# PCB_Telemetria_2020.net
KiCad netlist of a schematic drawn in EAGLE
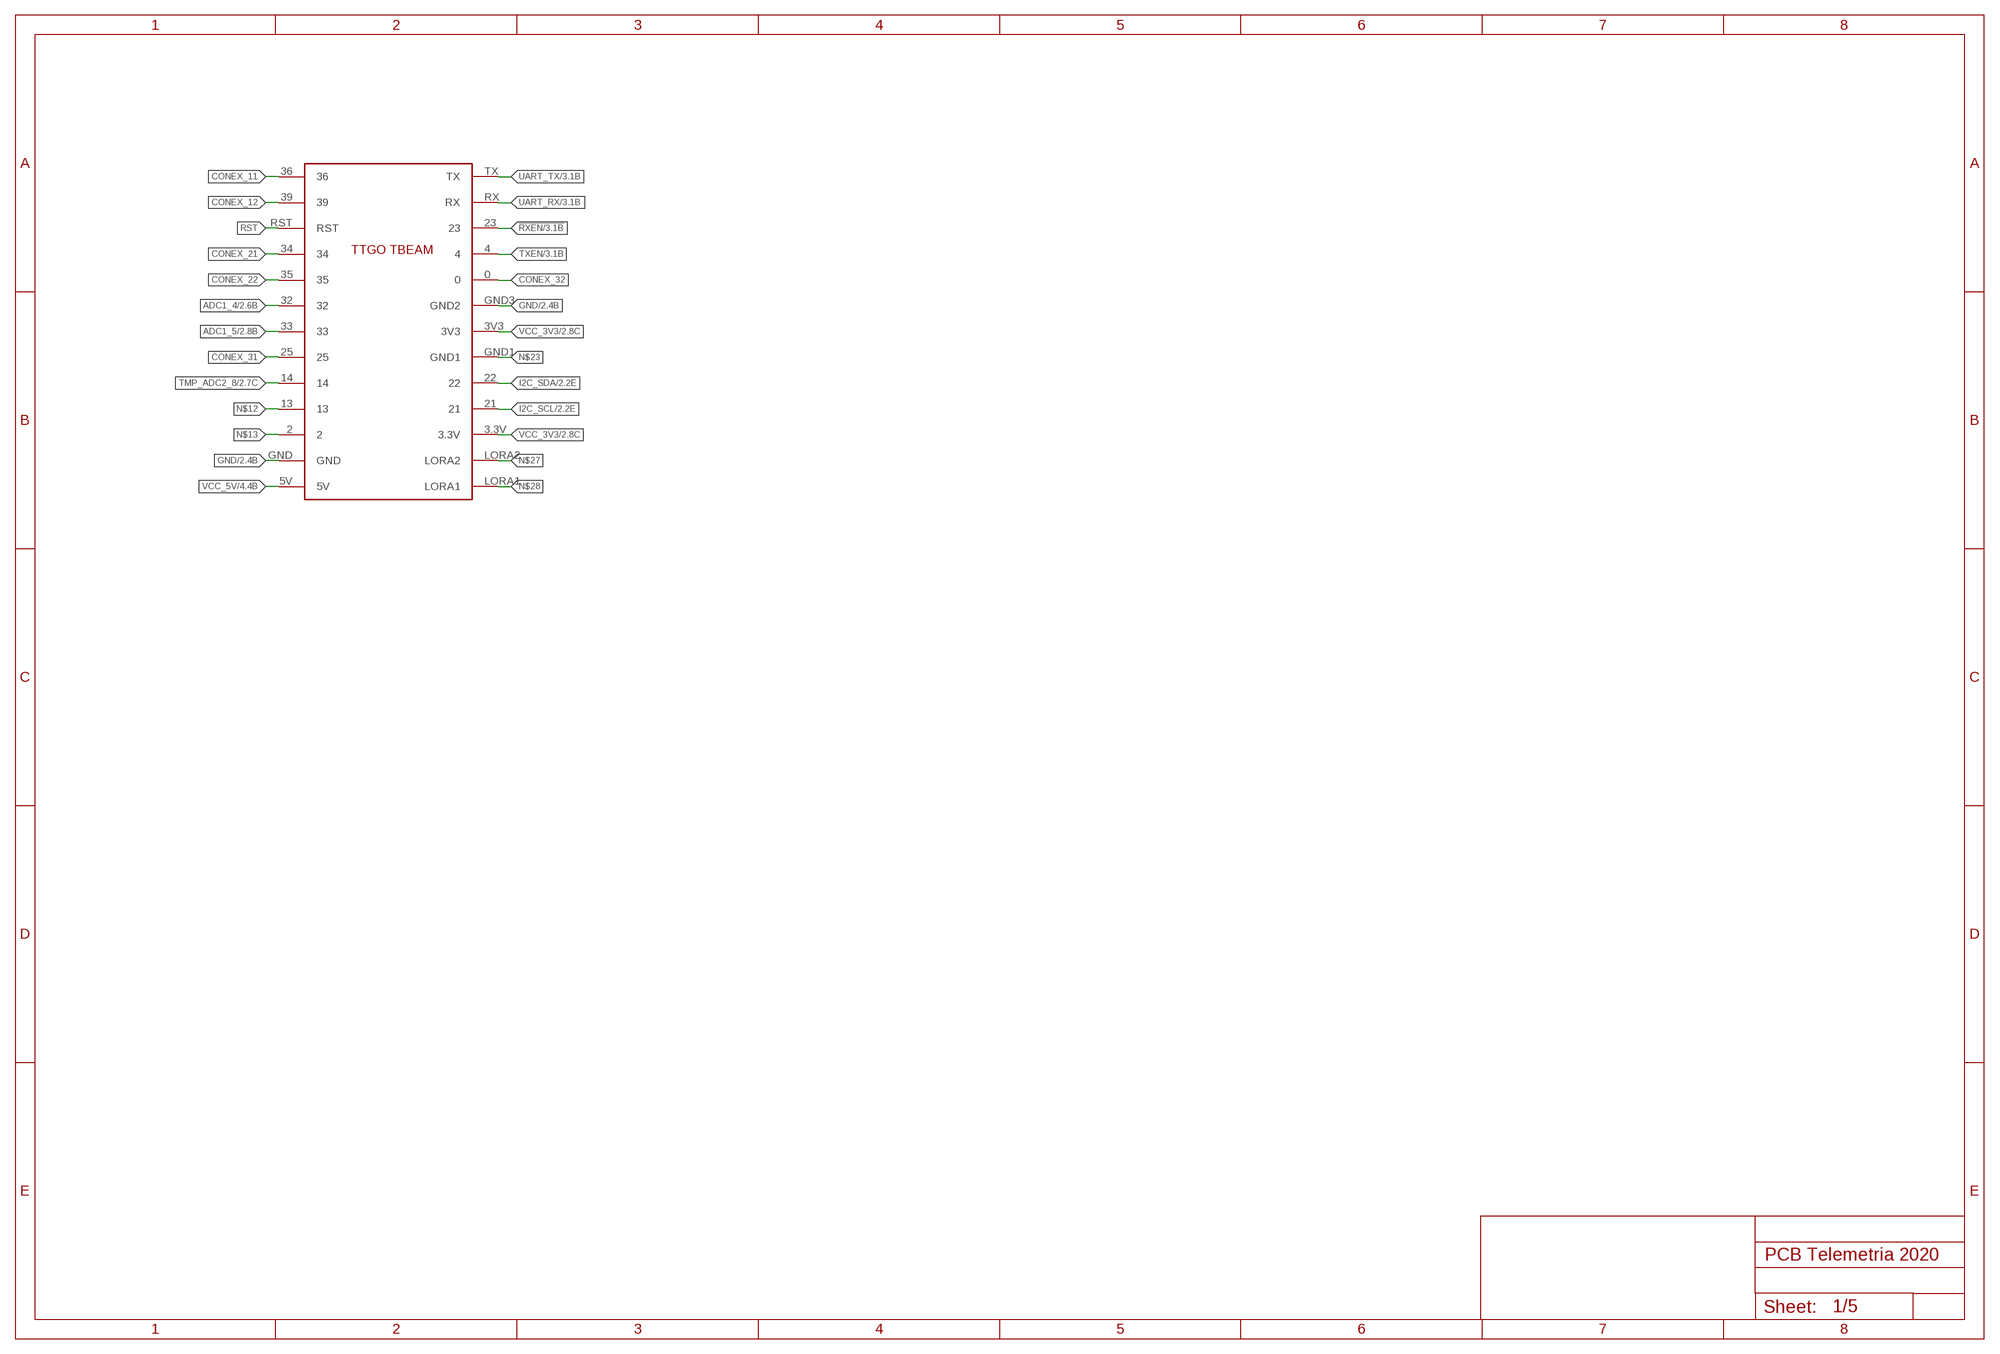
[diagram p0: schematic, sheet 1]
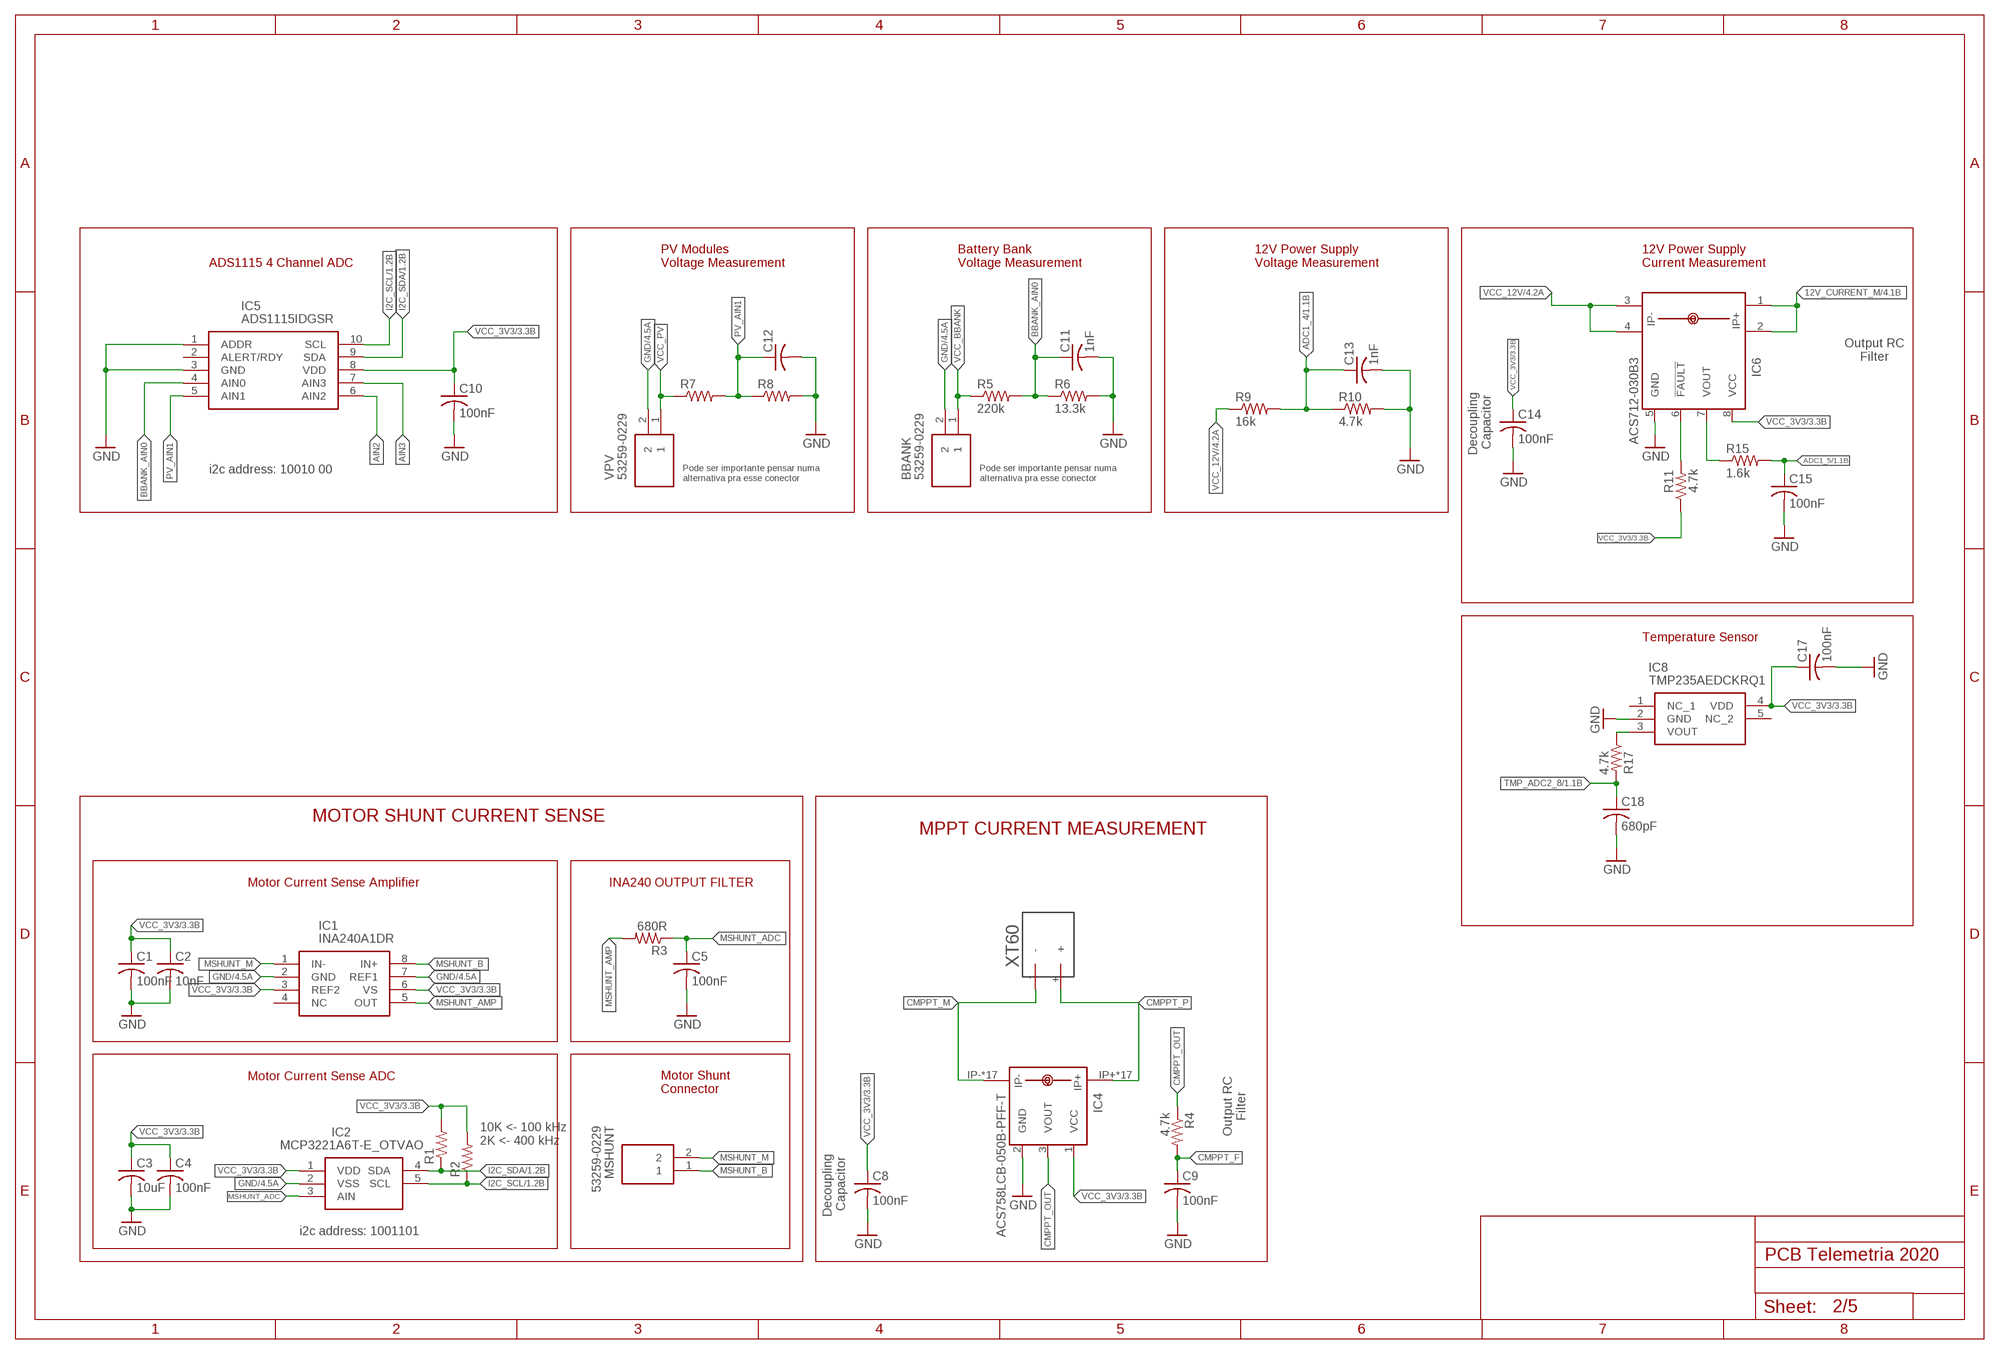
[diagram p1: schematic, sheet 2]
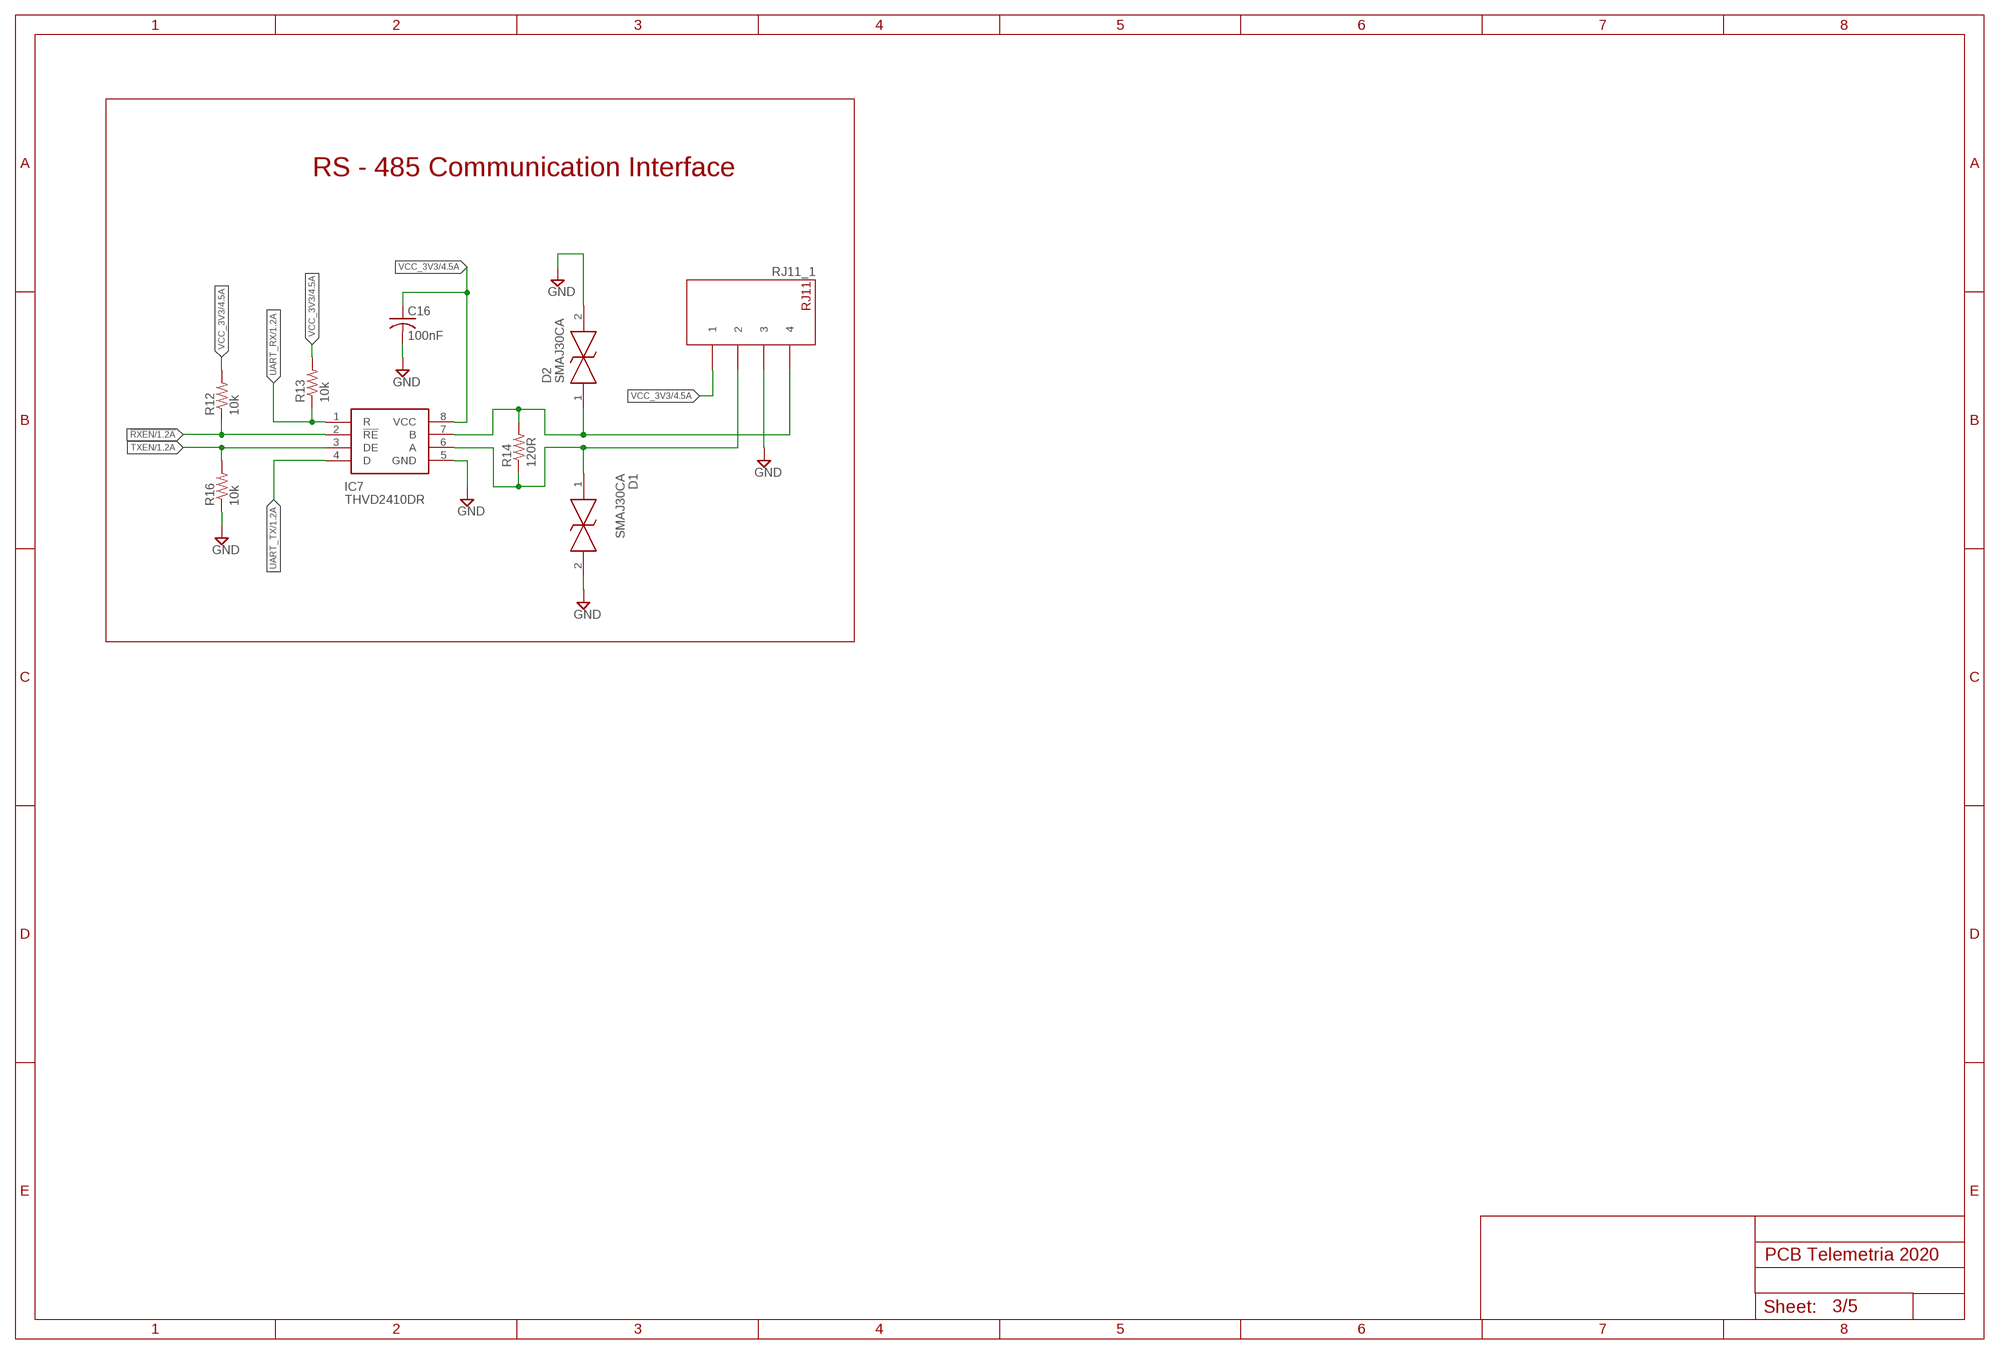
[diagram p2: schematic, sheet 3]
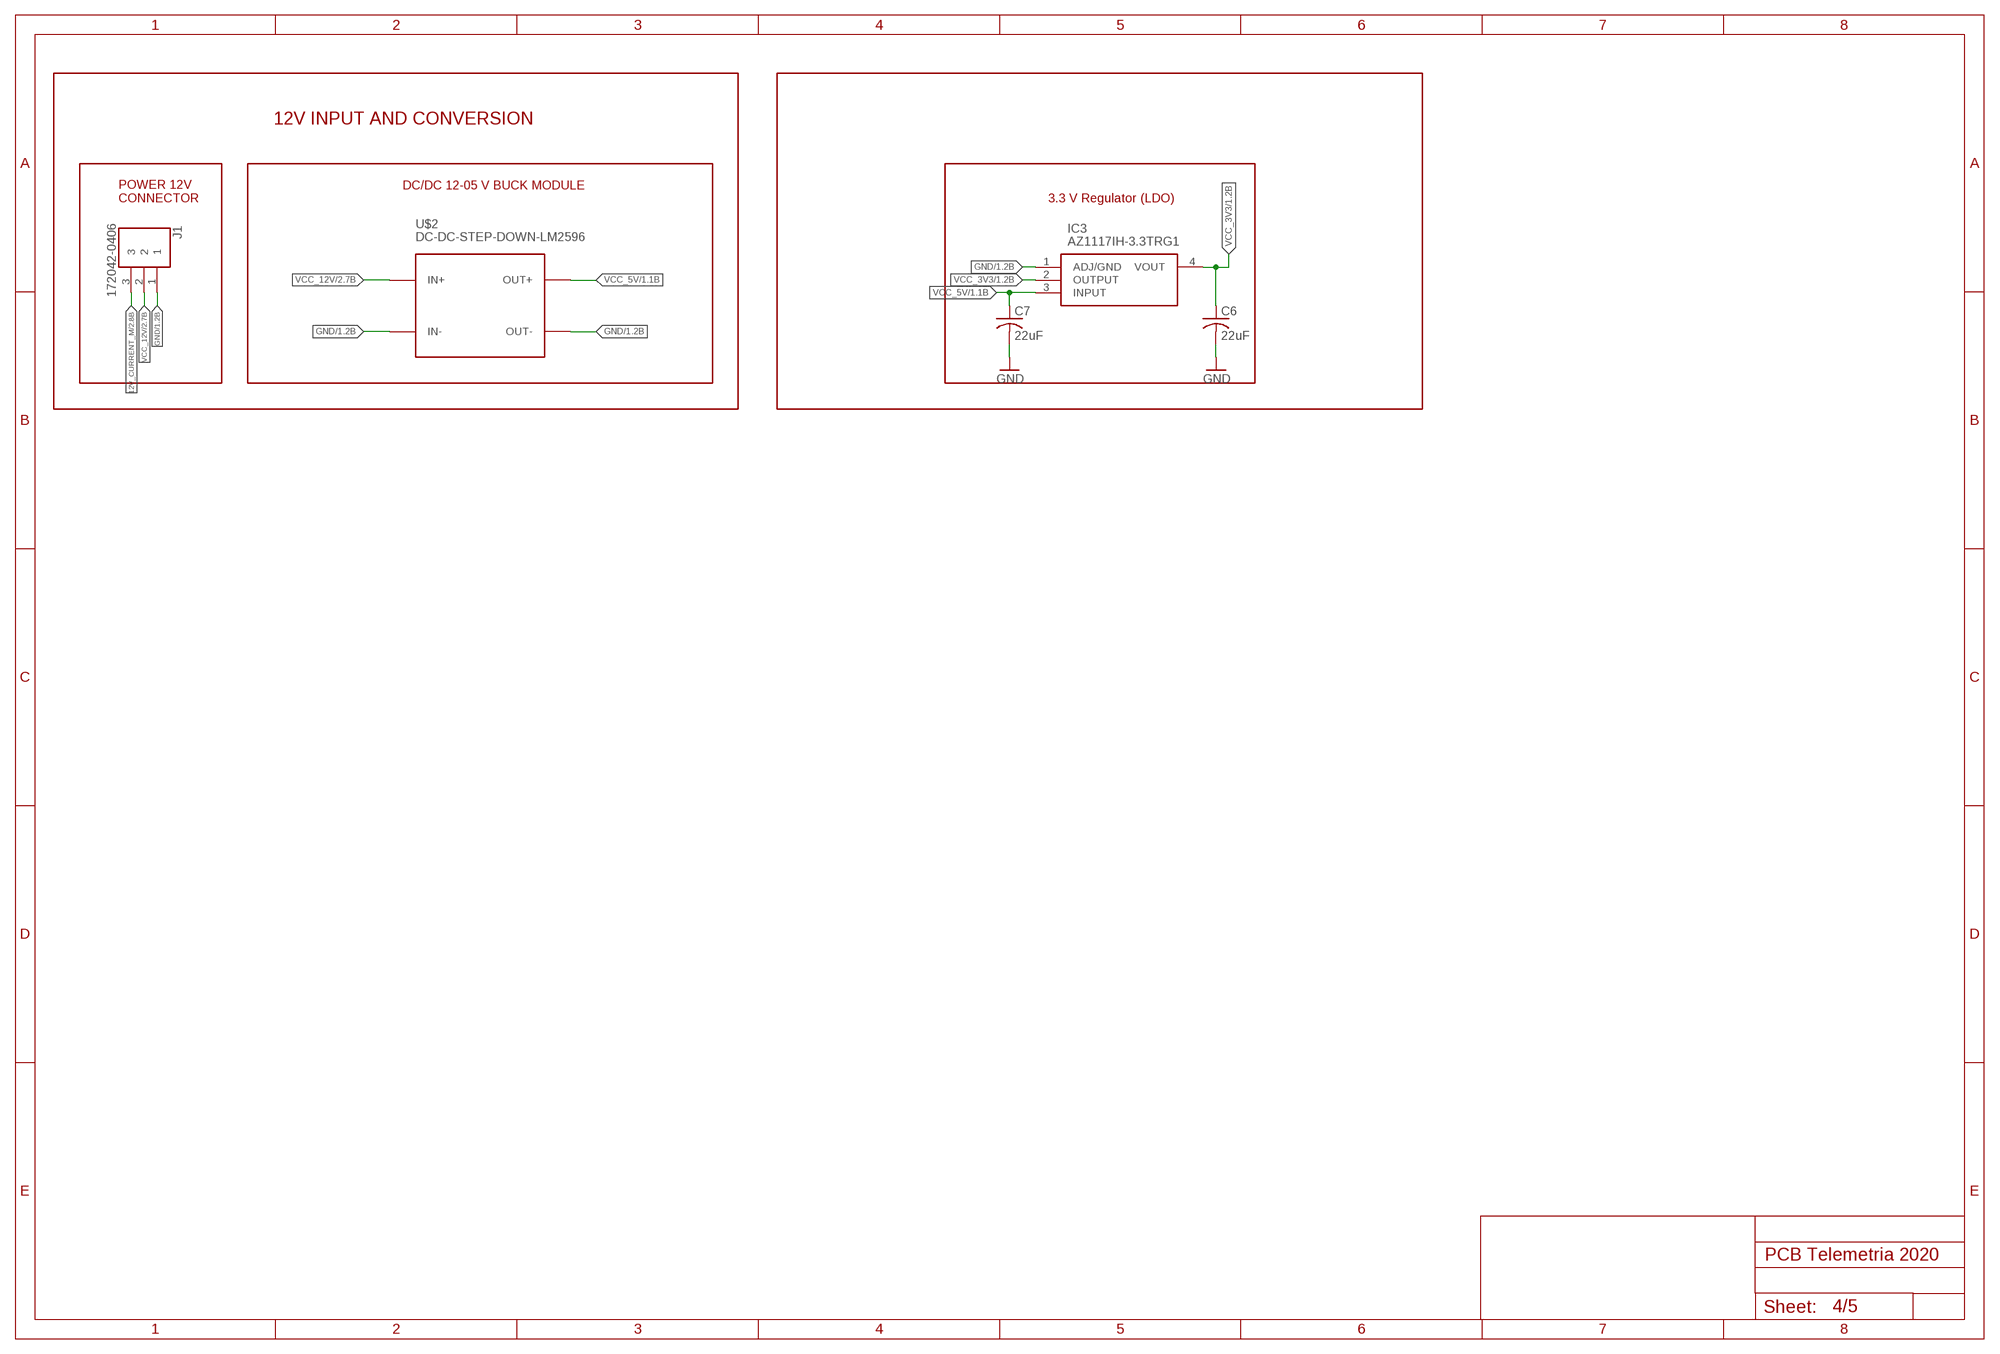
[diagram p3: schematic, sheet 4]
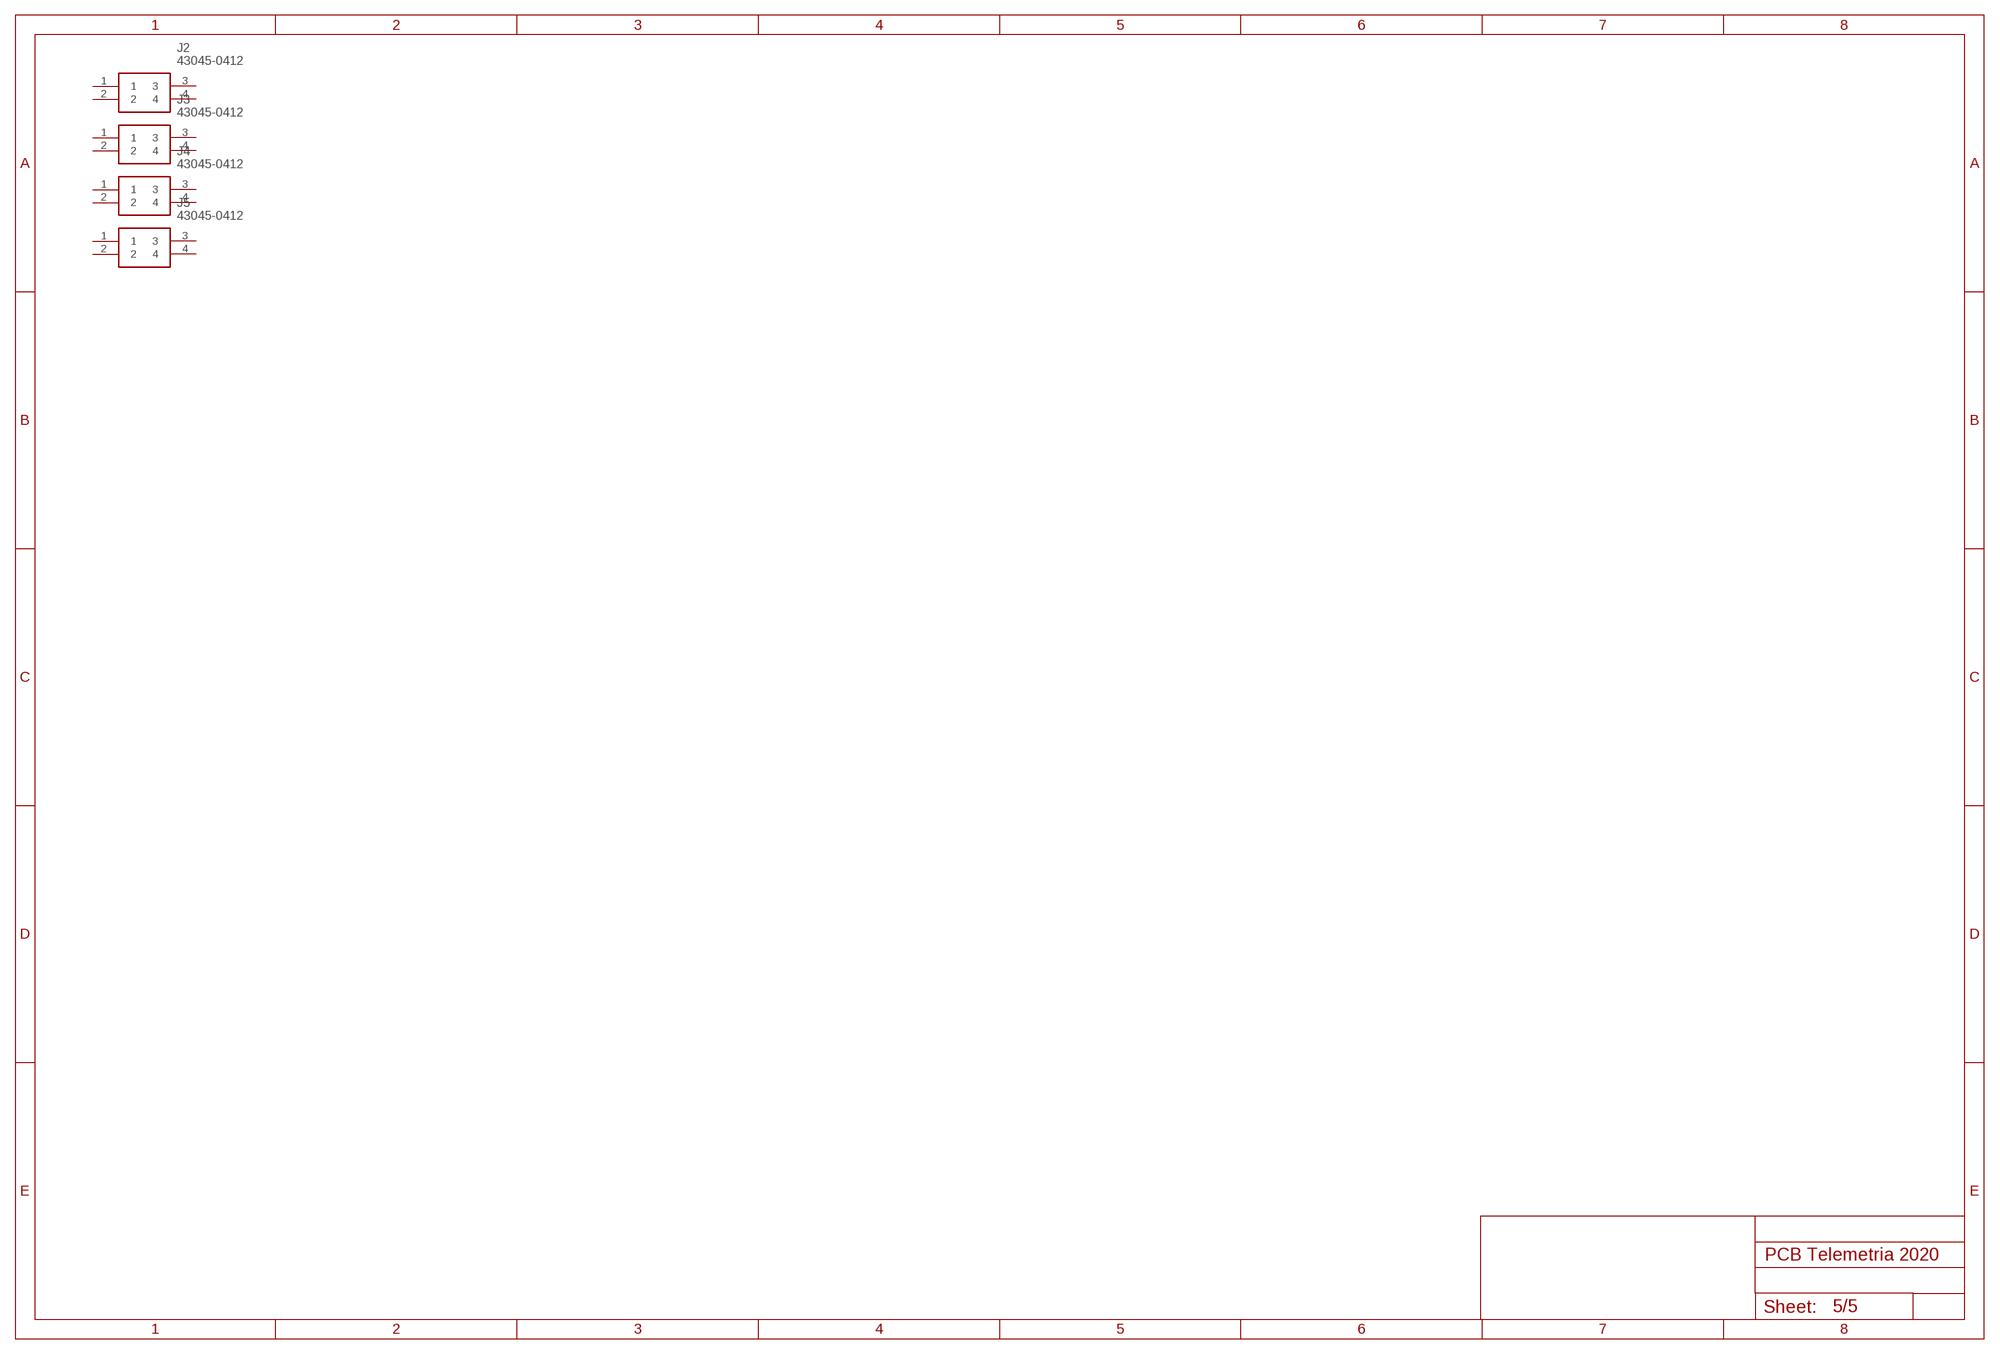
[diagram p4: schematic, sheet 5]

(export (version "E")
  (design (tool "Eeschema 10.0.6"))
  (components
    (comp (ref "C16")
      (value "100nF")
      (footprint "eagle-import:C0805")
      (libsource (lib "eagle-import") (part "C-USC0805"))
    )
    (comp (ref "D1")
      (value "SMAJ30CA")
      (footprint "eagle-import:DIONM5026X229N")
      (fields (field (name "MOUSER_PART_NUMBER") "576-SMAJ30CA"))
      (libsource (lib "eagle-import") (part "SMAJ30CA"))
    )
    (comp (ref "D2")
      (value "SMAJ30CA")
      (footprint "eagle-import:DIONM5026X229N")
      (fields (field (name "MOUSER_PART_NUMBER") "576-SMAJ30CA"))
      (libsource (lib "eagle-import") (part "SMAJ30CA"))
    )
    (comp (ref "IC7")
      (value "THVD2410DR")
      (footprint "eagle-import:SOIC127P600X175-8N")
      (fields (field (name "MOUSER_PART_NUMBER") "595-THVD2410DR"))
      (libsource (lib "eagle-import") (part "THVD2410DR"))
    )
    (comp (ref "R12")
      (value "10k")
      (footprint "eagle-import:M0805")
      (libsource (lib "eagle-import") (part "R-US_M0805"))
    )
    (comp (ref "R13")
      (value "10k")
      (footprint "eagle-import:M0805")
      (libsource (lib "eagle-import") (part "R-US_M0805"))
    )
    (comp (ref "R14")
      (value "120R")
      (footprint "eagle-import:M0805")
      (libsource (lib "eagle-import") (part "R-US_M0805"))
    )
    (comp (ref "R16")
      (value "10k")
      (footprint "eagle-import:M0805")
      (libsource (lib "eagle-import") (part "R-US_M0805"))
    )
    (comp (ref "RJ11_1")
      (value "TFC44")
      (footprint "eagle-import:TFC44")
      (libsource (lib "eagle-import") (part "TFC44"))
    )
    (comp (ref "C6")
      (value "22uF")
      (footprint "eagle-import:C0805")
      (libsource (lib "eagle-import") (part "C-USC0805"))
    )
    (comp (ref "C7")
      (value "22uF")
      (footprint "eagle-import:C0805")
      (libsource (lib "eagle-import") (part "C-USC0805"))
    )
    (comp (ref "IC3")
      (value "AZ1117IH-3.3TRG1")
      (footprint "eagle-import:SOT230P700X170-4N")
      (fields (field (name "MOUSER_PART_NUMBER") "621-AZ1117IH-3.3TRG1"))
      (libsource (lib "eagle-import") (part "AZ1117IH-3.3TRG1"))
    )
    (comp (ref "J1")
      (value "172042-0406")
      (footprint "eagle-import:MOLEX_172042-0406")
      (fields (field (name "MF") "Molex") (field (name "MP") "172042-0302"))
      (libsource (lib "eagle-import") (part "172042-0406"))
    )
    (comp (ref "U$2")
      (value "DC-DC-STEP-DOWN-LM2596")
      (footprint "eagle-import:DC-DC-STEP-DOWN-LM2596")
      (libsource (lib "eagle-import") (part "DC-DC-STEP-DOWN-LM2596"))
    )
    (comp (ref "BBANK")
      (value "53259-0229")
      (footprint "eagle-import:0532590229")
      (fields (field (name "MOUSER_PART_NUMBER") "538-53259-0229"))
      (libsource (lib "eagle-import") (part "53259-0229"))
    )
    (comp (ref "C1")
      (value "100nF")
      (footprint "eagle-import:C0805")
      (libsource (lib "eagle-import") (part "C-USC0805"))
    )
    (comp (ref "C2")
      (value "10nF")
      (footprint "eagle-import:C0805")
      (libsource (lib "eagle-import") (part "C-USC0805"))
    )
    (comp (ref "C3")
      (value "10uF")
      (footprint "eagle-import:C0805")
      (libsource (lib "eagle-import") (part "C-USC0805"))
    )
    (comp (ref "C4")
      (value "100nF")
      (footprint "eagle-import:C0805")
      (libsource (lib "eagle-import") (part "C-USC0805"))
    )
    (comp (ref "C5")
      (value "100nF")
      (footprint "eagle-import:C0805")
      (libsource (lib "eagle-import") (part "C-USC0805"))
    )
    (comp (ref "C8")
      (value "100nF")
      (footprint "eagle-import:C0805")
      (libsource (lib "eagle-import") (part "C-USC0805"))
    )
    (comp (ref "C9")
      (value "100nF")
      (footprint "eagle-import:C0805")
      (libsource (lib "eagle-import") (part "C-USC0805"))
    )
    (comp (ref "C10")
      (value "100nF")
      (footprint "eagle-import:C0805")
      (libsource (lib "eagle-import") (part "C-USC0805"))
    )
    (comp (ref "C11")
      (value "1nF")
      (footprint "eagle-import:C0805")
      (libsource (lib "eagle-import") (part "C-USC0805"))
    )
    (comp (ref "C12")
      (value "C-USC0805")
      (footprint "eagle-import:C0805")
      (libsource (lib "eagle-import") (part "C-USC0805"))
    )
    (comp (ref "C13")
      (value "1nF")
      (footprint "eagle-import:C0805")
      (libsource (lib "eagle-import") (part "C-USC0805"))
    )
    (comp (ref "C14")
      (value "100nF")
      (footprint "eagle-import:C0805")
      (libsource (lib "eagle-import") (part "C-USC0805"))
    )
    (comp (ref "C15")
      (value "100nF")
      (footprint "eagle-import:C0805")
      (libsource (lib "eagle-import") (part "C-USC0805"))
    )
    (comp (ref "C17")
      (value "100nF")
      (footprint "eagle-import:C0805")
      (libsource (lib "eagle-import") (part "C-USC0805"))
    )
    (comp (ref "C18")
      (value "680pF")
      (footprint "eagle-import:C0805")
      (libsource (lib "eagle-import") (part "C-USC0805"))
    )
    (comp (ref "IC1")
      (value "INA240A1DR")
      (footprint "eagle-import:SOIC127P600X175-8N")
      (fields (field (name "MOUSER_PART_NUMBER") "595-INA240A1DR"))
      (libsource (lib "eagle-import") (part "INA240A1DR"))
    )
    (comp (ref "IC2")
      (value "MCP3221A6T-E_OTVAO")
      (footprint "eagle-import:SOT95P280X145-5N")
      (fields
        (field (name "MANUFACTURER_PART_NUMBER") "MCP3221A6T-E/OTVAO")
        (field (name "MOUSER_PART_NUMBER") "579-MCP3221A6TEOTVAO")
      )
      (libsource (lib "eagle-import") (part "MCP3221A6T-E_OTVAO"))
    )
    (comp (ref "IC4")
      (value "ACS758LCB-050B-PFF-T")
      (footprint "eagle-import:CB-PFF")
      (libsource (lib "eagle-import") (part "ACS758LCB-050B-PFF-T"))
    )
    (comp (ref "IC5")
      (value "ADS1115IDGSR")
      (footprint "eagle-import:SOP50P490X110-10N")
      (fields (field (name "MOUSER_PART_NUMBER") "595-ADS1115IDGSR"))
      (libsource (lib "eagle-import") (part "ADS1115IDGSR"))
    )
    (comp (ref "IC6")
      (value "ACS712-030B3")
      (footprint "eagle-import:SOIC8")
      (libsource (lib "eagle-import") (part "ACS712-LC"))
    )
    (comp (ref "IC8")
      (value "TMP235AEDCKRQ1")
      (footprint "eagle-import:SOT65P210X110-5N")
      (fields (field (name "MOUSER_PART_NUMBER") "595-TMP235AEDCKRQ1"))
      (libsource (lib "eagle-import") (part "TMP235AEDCKRQ1"))
    )
    (comp (ref "MSHUNT")
      (value "53259-0229")
      (footprint "eagle-import:0532590229")
      (fields (field (name "MOUSER_PART_NUMBER") "538-53259-0229"))
      (libsource (lib "eagle-import") (part "53259-0229"))
    )
    (comp (ref "R1")
      (value "R-US_R0805")
      (footprint "eagle-import:R0805")
      (libsource (lib "eagle-import") (part "R-US_R0805"))
    )
    (comp (ref "R2")
      (value "R-US_R0805")
      (footprint "eagle-import:R0805")
      (libsource (lib "eagle-import") (part "R-US_R0805"))
    )
    (comp (ref "R3")
      (value "680R")
      (footprint "eagle-import:R0805")
      (libsource (lib "eagle-import") (part "R-US_R0805"))
    )
    (comp (ref "R4")
      (value "4.7k")
      (footprint "eagle-import:R0805")
      (libsource (lib "eagle-import") (part "R-US_R0805"))
    )
    (comp (ref "R5")
      (value "220k")
      (footprint "eagle-import:R0805")
      (libsource (lib "eagle-import") (part "R-US_R0805"))
    )
    (comp (ref "R6")
      (value "13.3k")
      (footprint "eagle-import:R0805")
      (libsource (lib "eagle-import") (part "R-US_R0805"))
    )
    (comp (ref "R7")
      (value "R-US_R0805")
      (footprint "eagle-import:R0805")
      (libsource (lib "eagle-import") (part "R-US_R0805"))
    )
    (comp (ref "R8")
      (value "R-US_R0805")
      (footprint "eagle-import:R0805")
      (libsource (lib "eagle-import") (part "R-US_R0805"))
    )
    (comp (ref "R9")
      (value "16k")
      (footprint "eagle-import:R0805")
      (libsource (lib "eagle-import") (part "R-US_R0805"))
    )
    (comp (ref "R10")
      (value "4.7k")
      (footprint "eagle-import:R0805")
      (libsource (lib "eagle-import") (part "R-US_R0805"))
    )
    (comp (ref "R11")
      (value "4.7k")
      (footprint "eagle-import:R0805")
      (libsource (lib "eagle-import") (part "R-US_R0805"))
    )
    (comp (ref "R15")
      (value "1.6k")
      (footprint "eagle-import:R0805")
      (libsource (lib "eagle-import") (part "R-US_R0805"))
    )
    (comp (ref "R17")
      (value "4.7k")
      (footprint "eagle-import:R0805")
      (libsource (lib "eagle-import") (part "R-US_R0805"))
    )
    (comp (ref "U$3")
      (value "XT60")
      (footprint "eagle-import:XT60")
      (libsource (lib "eagle-import") (part "XT60"))
    )
    (comp (ref "VPV")
      (value "53259-0229")
      (footprint "eagle-import:0532590229")
      (fields (field (name "MOUSER_PART_NUMBER") "538-53259-0229"))
      (libsource (lib "eagle-import") (part "53259-0229"))
    )
    (comp (ref "U$1")
      (value "TTGOBEAM")
      (footprint "eagle-import:TTGOBEAM")
      (libsource (lib "eagle-import") (part "TTGOBEAM"))
    )
    (comp (ref "J2")
      (value "43045-0412")
      (footprint "eagle-import:43045-0412")
      (fields (field (name "MOUSER_PART_NUMBER") "538-43045-0412"))
      (libsource (lib "eagle-import") (part "43045-0412"))
    )
    (comp (ref "J3")
      (value "43045-0412")
      (footprint "eagle-import:43045-0412")
      (fields (field (name "MOUSER_PART_NUMBER") "538-43045-0412"))
      (libsource (lib "eagle-import") (part "43045-0412"))
    )
    (comp (ref "J4")
      (value "43045-0412")
      (footprint "eagle-import:43045-0412")
      (fields (field (name "MOUSER_PART_NUMBER") "538-43045-0412"))
      (libsource (lib "eagle-import") (part "43045-0412"))
    )
    (comp (ref "J5")
      (value "43045-0412")
      (footprint "eagle-import:43045-0412")
      (fields (field (name "MOUSER_PART_NUMBER") "538-43045-0412"))
      (libsource (lib "eagle-import") (part "43045-0412"))
    )
  )
  (nets
    (net (code "1") (name "12V_CURRENT_M") (class "Default")
      (node (ref "IC6") (pin "1") (pinfunction "IP+_1") (pintype "passive"))
      (node (ref "IC6") (pin "2") (pinfunction "IP+1_2") (pintype "passive"))
      (node (ref "J1") (pin "3") (pinfunction "3_3") (pintype "passive"))
    )
    (net (code "2") (name "ADC1_4") (class "Default")
      (node (ref "C13") (pin "1") (pinfunction "1_1") (pintype "passive"))
      (node (ref "R10") (pin "1") (pinfunction "1_1") (pintype "passive"))
      (node (ref "R9") (pin "2") (pinfunction "2_2") (pintype "passive"))
      (node (ref "U$1") (pin "32") (pinfunction "32_32") (pintype "bidirectional"))
    )
    (net (code "3") (name "ADC1_5") (class "Default")
      (node (ref "C15") (pin "1") (pinfunction "1_1") (pintype "passive"))
      (node (ref "R15") (pin "2") (pinfunction "2_2") (pintype "passive"))
      (node (ref "U$1") (pin "33") (pinfunction "33_33") (pintype "bidirectional"))
    )
    (net (code "4") (name "AIN2") (class "Default")
      (node (ref "IC5") (pin "6") (pinfunction "AIN2_6") (pintype "bidirectional"))
    )
    (net (code "5") (name "AIN3") (class "Default")
      (node (ref "IC5") (pin "7") (pinfunction "AIN3_7") (pintype "bidirectional"))
    )
    (net (code "6") (name "BBANK_AIN0") (class "Default")
      (node (ref "C11") (pin "1") (pinfunction "1_1") (pintype "passive"))
      (node (ref "IC5") (pin "4") (pinfunction "AIN0_4") (pintype "bidirectional"))
      (node (ref "R5") (pin "2") (pinfunction "2_2") (pintype "passive"))
      (node (ref "R6") (pin "1") (pinfunction "1_1") (pintype "passive"))
    )
    (net (code "7") (name "CMPPT_F") (class "Default")
      (node (ref "C9") (pin "1") (pinfunction "1_1") (pintype "passive"))
      (node (ref "R4") (pin "2") (pinfunction "2_2") (pintype "passive"))
    )
    (net (code "8") (name "CMPPT_M") (class "Default")
      (node (ref "IC4") (pin "IP-") (pinfunction "IP-_IP-") (pintype "passive"))
      (node (ref "IC4") (pin "IP-@10") (pinfunction "IP-_IP-@10") (pintype "passive"))
      (node (ref "IC4") (pin "IP-@11") (pinfunction "IP-_IP-@11") (pintype "passive"))
      (node (ref "IC4") (pin "IP-@12") (pinfunction "IP-_IP-@12") (pintype "passive"))
      (node (ref "IC4") (pin "IP-@13") (pinfunction "IP-_IP-@13") (pintype "passive"))
      (node (ref "IC4") (pin "IP-@14") (pinfunction "IP-_IP-@14") (pintype "passive"))
      (node (ref "IC4") (pin "IP-@15") (pinfunction "IP-_IP-@15") (pintype "passive"))
      (node (ref "IC4") (pin "IP-@16") (pinfunction "IP-_IP-@16") (pintype "passive"))
      (node (ref "IC4") (pin "IP-@17") (pinfunction "IP-_IP-@17") (pintype "passive"))
      (node (ref "IC4") (pin "IP-@2") (pinfunction "IP-_IP-@2") (pintype "passive"))
      (node (ref "IC4") (pin "IP-@3") (pinfunction "IP-_IP-@3") (pintype "passive"))
      (node (ref "IC4") (pin "IP-@4") (pinfunction "IP-_IP-@4") (pintype "passive"))
      (node (ref "IC4") (pin "IP-@5") (pinfunction "IP-_IP-@5") (pintype "passive"))
      (node (ref "IC4") (pin "IP-@6") (pinfunction "IP-_IP-@6") (pintype "passive"))
      (node (ref "IC4") (pin "IP-@7") (pinfunction "IP-_IP-@7") (pintype "passive"))
      (node (ref "IC4") (pin "IP-@8") (pinfunction "IP-_IP-@8") (pintype "passive"))
      (node (ref "IC4") (pin "IP-@9") (pinfunction "IP-_IP-@9") (pintype "passive"))
      (node (ref "U$3") (pin "-") (pinfunction "-_-") (pintype "bidirectional"))
    )
    (net (code "9") (name "CMPPT_OUT") (class "Default")
      (node (ref "IC4") (pin "3") (pinfunction "VOUT_3") (pintype "output"))
      (node (ref "R4") (pin "1") (pinfunction "1_1") (pintype "passive"))
    )
    (net (code "10") (name "CMPPT_P") (class "Default")
      (node (ref "IC4") (pin "IP+") (pinfunction "IP+_IP+") (pintype "passive"))
      (node (ref "IC4") (pin "IP+@10") (pinfunction "IP+_IP+@10") (pintype "passive"))
      (node (ref "IC4") (pin "IP+@11") (pinfunction "IP+_IP+@11") (pintype "passive"))
      (node (ref "IC4") (pin "IP+@12") (pinfunction "IP+_IP+@12") (pintype "passive"))
      (node (ref "IC4") (pin "IP+@13") (pinfunction "IP+_IP+@13") (pintype "passive"))
      (node (ref "IC4") (pin "IP+@14") (pinfunction "IP+_IP+@14") (pintype "passive"))
      (node (ref "IC4") (pin "IP+@15") (pinfunction "IP+_IP+@15") (pintype "passive"))
      (node (ref "IC4") (pin "IP+@16") (pinfunction "IP+_IP+@16") (pintype "passive"))
      (node (ref "IC4") (pin "IP+@17") (pinfunction "IP+_IP+@17") (pintype "passive"))
      (node (ref "IC4") (pin "IP+@2") (pinfunction "IP+_IP+@2") (pintype "passive"))
      (node (ref "IC4") (pin "IP+@3") (pinfunction "IP+_IP+@3") (pintype "passive"))
      (node (ref "IC4") (pin "IP+@4") (pinfunction "IP+_IP+@4") (pintype "passive"))
      (node (ref "IC4") (pin "IP+@5") (pinfunction "IP+_IP+@5") (pintype "passive"))
      (node (ref "IC4") (pin "IP+@6") (pinfunction "IP+_IP+@6") (pintype "passive"))
      (node (ref "IC4") (pin "IP+@7") (pinfunction "IP+_IP+@7") (pintype "passive"))
      (node (ref "IC4") (pin "IP+@8") (pinfunction "IP+_IP+@8") (pintype "passive"))
      (node (ref "IC4") (pin "IP+@9") (pinfunction "IP+_IP+@9") (pintype "passive"))
      (node (ref "U$3") (pin "+") (pinfunction "+_+") (pintype "bidirectional"))
    )
    (net (code "11") (name "CONEX_11") (class "Default")
      (node (ref "U$1") (pin "36") (pinfunction "36_36") (pintype "bidirectional"))
    )
    (net (code "12") (name "CONEX_12") (class "Default")
      (node (ref "U$1") (pin "39") (pinfunction "39_39") (pintype "bidirectional"))
    )
    (net (code "13") (name "CONEX_21") (class "Default")
      (node (ref "U$1") (pin "34") (pinfunction "34_34") (pintype "bidirectional"))
    )
    (net (code "14") (name "CONEX_22") (class "Default")
      (node (ref "U$1") (pin "35") (pinfunction "35_35") (pintype "bidirectional"))
    )
    (net (code "15") (name "CONEX_31") (class "Default")
      (node (ref "U$1") (pin "25") (pinfunction "25_25") (pintype "bidirectional"))
    )
    (net (code "16") (name "CONEX_32") (class "Default")
      (node (ref "U$1") (pin "0") (pinfunction "0_0") (pintype "bidirectional"))
    )
    (net (code "17") (name "GND") (class "Default")
      (node (ref "BBANK") (pin "2") (pinfunction "2_2") (pintype "bidirectional"))
      (node (ref "C1") (pin "2") (pinfunction "2_2") (pintype "passive"))
      (node (ref "C10") (pin "2") (pinfunction "2_2") (pintype "passive"))
      (node (ref "C11") (pin "2") (pinfunction "2_2") (pintype "passive"))
      (node (ref "C12") (pin "2") (pinfunction "2_2") (pintype "passive"))
      (node (ref "C13") (pin "2") (pinfunction "2_2") (pintype "passive"))
      (node (ref "C14") (pin "2") (pinfunction "2_2") (pintype "passive"))
      (node (ref "C15") (pin "2") (pinfunction "2_2") (pintype "passive"))
      (node (ref "C16") (pin "2") (pinfunction "2_2") (pintype "passive"))
      (node (ref "C17") (pin "2") (pinfunction "2_2") (pintype "passive"))
      (node (ref "C18") (pin "2") (pinfunction "2_2") (pintype "passive"))
      (node (ref "C2") (pin "2") (pinfunction "2_2") (pintype "passive"))
      (node (ref "C3") (pin "2") (pinfunction "2_2") (pintype "passive"))
      (node (ref "C4") (pin "2") (pinfunction "2_2") (pintype "passive"))
      (node (ref "C5") (pin "2") (pinfunction "2_2") (pintype "passive"))
      (node (ref "C6") (pin "2") (pinfunction "2_2") (pintype "passive"))
      (node (ref "C7") (pin "2") (pinfunction "2_2") (pintype "passive"))
      (node (ref "C8") (pin "2") (pinfunction "2_2") (pintype "passive"))
      (node (ref "C9") (pin "2") (pinfunction "2_2") (pintype "passive"))
      (node (ref "D1") (pin "2") (pinfunction "2_2") (pintype "bidirectional"))
      (node (ref "D2") (pin "2") (pinfunction "2_2") (pintype "bidirectional"))
      (node (ref "IC1") (pin "2") (pinfunction "GND_2") (pintype "bidirectional"))
      (node (ref "IC1") (pin "7") (pinfunction "REF1_7") (pintype "bidirectional"))
      (node (ref "IC2") (pin "2") (pinfunction "VSS_2") (pintype "bidirectional"))
      (node (ref "IC3") (pin "1") (pinfunction "ADJ/GND_1") (pintype "bidirectional"))
      (node (ref "IC4") (pin "2") (pinfunction "GND_2") (pintype "power_in"))
      (node (ref "IC5") (pin "1") (pinfunction "ADDR_1") (pintype "bidirectional"))
      (node (ref "IC5") (pin "3") (pinfunction "GND_3") (pintype "bidirectional"))
      (node (ref "IC6") (pin "5") (pinfunction "GND_5") (pintype "power_in"))
      (node (ref "IC7") (pin "5") (pinfunction "GND_5") (pintype "bidirectional"))
      (node (ref "IC8") (pin "2") (pinfunction "GND_2") (pintype "bidirectional"))
      (node (ref "J1") (pin "1") (pinfunction "1_1") (pintype "passive"))
      (node (ref "R10") (pin "2") (pinfunction "2_2") (pintype "passive"))
      (node (ref "R16") (pin "1") (pinfunction "1_1") (pintype "passive"))
      (node (ref "R6") (pin "2") (pinfunction "2_2") (pintype "passive"))
      (node (ref "R8") (pin "2") (pinfunction "2_2") (pintype "passive"))
      (node (ref "RJ11_1") (pin "P$3") (pinfunction "3_P$3") (pintype "bidirectional"))
      (node (ref "U$1") (pin "GND") (pinfunction "GND_GND") (pintype "bidirectional"))
      (node (ref "U$1") (pin "GND3") (pinfunction "GND2_GND3") (pintype "bidirectional"))
      (node (ref "U$2") (pin "IN-") (pinfunction "IN-_IN-") (pintype "bidirectional"))
      (node (ref "U$2") (pin "OUT-") (pinfunction "OUT-_OUT-") (pintype "bidirectional"))
      (node (ref "VPV") (pin "2") (pinfunction "2_2") (pintype "bidirectional"))
    )
    (net (code "18") (name "I2C_SCL") (class "Default")
      (node (ref "IC2") (pin "5") (pinfunction "SCL_5") (pintype "bidirectional"))
      (node (ref "IC5") (pin "10") (pinfunction "SCL_10") (pintype "bidirectional"))
      (node (ref "R2") (pin "1") (pinfunction "1_1") (pintype "passive"))
      (node (ref "U$1") (pin "21") (pinfunction "21_21") (pintype "bidirectional"))
    )
    (net (code "19") (name "I2C_SDA") (class "Default")
      (node (ref "IC2") (pin "4") (pinfunction "SDA_4") (pintype "bidirectional"))
      (node (ref "IC5") (pin "9") (pinfunction "SDA_9") (pintype "bidirectional"))
      (node (ref "R1") (pin "1") (pinfunction "1_1") (pintype "passive"))
      (node (ref "U$1") (pin "22") (pinfunction "22_22") (pintype "bidirectional"))
    )
    (net (code "20") (name "MSHUNT_ADC") (class "Default")
      (node (ref "C5") (pin "1") (pinfunction "1_1") (pintype "passive"))
      (node (ref "IC2") (pin "3") (pinfunction "AIN_3") (pintype "bidirectional"))
      (node (ref "R3") (pin "1") (pinfunction "1_1") (pintype "passive"))
    )
    (net (code "21") (name "MSHUNT_AMP") (class "Default")
      (node (ref "IC1") (pin "5") (pinfunction "OUT_5") (pintype "bidirectional"))
      (node (ref "R3") (pin "2") (pinfunction "2_2") (pintype "passive"))
    )
    (net (code "22") (name "MSHUNT_B") (class "Default")
      (node (ref "IC1") (pin "8") (pinfunction "IN+_8") (pintype "bidirectional"))
      (node (ref "MSHUNT") (pin "1") (pinfunction "1_1") (pintype "bidirectional"))
    )
    (net (code "23") (name "MSHUNT_M") (class "Default")
      (node (ref "IC1") (pin "1") (pinfunction "IN-_1") (pintype "bidirectional"))
      (node (ref "MSHUNT") (pin "2") (pinfunction "2_2") (pintype "bidirectional"))
    )
    (net (code "24") (name "N$12") (class "Default")
      (node (ref "U$1") (pin "13") (pinfunction "13_13") (pintype "bidirectional"))
    )
    (net (code "25") (name "N$13") (class "Default")
      (node (ref "U$1") (pin "2") (pinfunction "2_2") (pintype "bidirectional"))
    )
    (net (code "26") (name "N$23") (class "Default")
      (node (ref "U$1") (pin "GND1") (pinfunction "GND1_GND1") (pintype "bidirectional"))
    )
    (net (code "27") (name "N$27") (class "Default")
      (node (ref "U$1") (pin "LORA2") (pinfunction "LORA2_LORA2") (pintype "bidirectional"))
    )
    (net (code "28") (name "N$28") (class "Default")
      (node (ref "U$1") (pin "LORA1") (pinfunction "LORA1_LORA1") (pintype "bidirectional"))
    )
    (net (code "29") (name "Net-(IC6-VOUT)") (class "Default")
      (node (ref "IC6") (pin "7") (pinfunction "VOUT_7") (pintype "output"))
      (node (ref "R15") (pin "1") (pinfunction "1_1") (pintype "passive"))
    )
    (net (code "30") (name "Net-(IC6-~{FAULT})") (class "Default")
      (node (ref "IC6") (pin "6") (pinfunction "~{FAULT}_6") (pintype "bidirectional"))
      (node (ref "R11") (pin "2") (pinfunction "2_2") (pintype "passive"))
    )
    (net (code "31") (name "Net-(IC7-A)") (class "Default")
      (node (ref "D1") (pin "1") (pinfunction "1_1") (pintype "bidirectional"))
      (node (ref "IC7") (pin "6") (pinfunction "A_6") (pintype "bidirectional"))
      (node (ref "R14") (pin "1") (pinfunction "1_1") (pintype "passive"))
      (node (ref "RJ11_1") (pin "P$2") (pinfunction "2_P$2") (pintype "bidirectional"))
    )
    (net (code "32") (name "Net-(IC7-B)") (class "Default")
      (node (ref "D2") (pin "1") (pinfunction "1_1") (pintype "bidirectional"))
      (node (ref "IC7") (pin "7") (pinfunction "B_7") (pintype "bidirectional"))
      (node (ref "R14") (pin "2") (pinfunction "2_2") (pintype "passive"))
      (node (ref "RJ11_1") (pin "P$4") (pinfunction "4_P$4") (pintype "bidirectional"))
    )
    (net (code "33") (name "Net-(IC8-VOUT)") (class "Default")
      (node (ref "IC8") (pin "3") (pinfunction "VOUT_3") (pintype "bidirectional"))
      (node (ref "R17") (pin "1") (pinfunction "1_1") (pintype "passive"))
    )
    (net (code "34") (name "PV_AIN1") (class "Default")
      (node (ref "C12") (pin "1") (pinfunction "1_1") (pintype "passive"))
      (node (ref "IC5") (pin "5") (pinfunction "AIN1_5") (pintype "bidirectional"))
      (node (ref "R7") (pin "2") (pinfunction "2_2") (pintype "passive"))
      (node (ref "R8") (pin "1") (pinfunction "1_1") (pintype "passive"))
    )
    (net (code "35") (name "RST") (class "Default")
      (node (ref "U$1") (pin "RST") (pinfunction "RST_RST") (pintype "bidirectional"))
    )
    (net (code "36") (name "TMP_ADC2_8") (class "Default")
      (node (ref "C18") (pin "1") (pinfunction "1_1") (pintype "passive"))
      (node (ref "R17") (pin "2") (pinfunction "2_2") (pintype "passive"))
      (node (ref "U$1") (pin "14") (pinfunction "14_14") (pintype "bidirectional"))
    )
    (net (code "37") (name "TXEN") (class "Default")
      (node (ref "IC7") (pin "3") (pinfunction "DE_3") (pintype "bidirectional"))
      (node (ref "R16") (pin "2") (pinfunction "2_2") (pintype "passive"))
      (node (ref "U$1") (pin "4") (pinfunction "4_4") (pintype "bidirectional"))
    )
    (net (code "38") (name "UART_RX") (class "Default")
      (node (ref "IC7") (pin "1") (pinfunction "R_1") (pintype "bidirectional"))
      (node (ref "R13") (pin "1") (pinfunction "1_1") (pintype "passive"))
      (node (ref "U$1") (pin "RX") (pinfunction "RX_RX") (pintype "bidirectional"))
    )
    (net (code "39") (name "UART_TX") (class "Default")
      (node (ref "IC7") (pin "4") (pinfunction "D_4") (pintype "bidirectional"))
      (node (ref "U$1") (pin "TX") (pinfunction "TX_TX") (pintype "bidirectional"))
    )
    (net (code "40") (name "VCC_3V3") (class "Default")
      (node (ref "C1") (pin "1") (pinfunction "1_1") (pintype "passive"))
      (node (ref "C10") (pin "1") (pinfunction "1_1") (pintype "passive"))
      (node (ref "C14") (pin "1") (pinfunction "1_1") (pintype "passive"))
      (node (ref "C16") (pin "1") (pinfunction "1_1") (pintype "passive"))
      (node (ref "C17") (pin "1") (pinfunction "1_1") (pintype "passive"))
      (node (ref "C2") (pin "1") (pinfunction "1_1") (pintype "passive"))
      (node (ref "C3") (pin "1") (pinfunction "1_1") (pintype "passive"))
      (node (ref "C4") (pin "1") (pinfunction "1_1") (pintype "passive"))
      (node (ref "C6") (pin "1") (pinfunction "1_1") (pintype "passive"))
      (node (ref "C8") (pin "1") (pinfunction "1_1") (pintype "passive"))
      (node (ref "IC1") (pin "3") (pinfunction "REF2_3") (pintype "bidirectional"))
      (node (ref "IC1") (pin "6") (pinfunction "VS_6") (pintype "bidirectional"))
      (node (ref "IC2") (pin "1") (pinfunction "VDD_1") (pintype "bidirectional"))
      (node (ref "IC3") (pin "2") (pinfunction "OUTPUT_2") (pintype "bidirectional"))
      (node (ref "IC3") (pin "4") (pinfunction "VOUT_4") (pintype "bidirectional"))
      (node (ref "IC4") (pin "1") (pinfunction "VCC_1") (pintype "power_in"))
      (node (ref "IC5") (pin "8") (pinfunction "VDD_8") (pintype "bidirectional"))
      (node (ref "IC6") (pin "8") (pinfunction "VCC_8") (pintype "power_in"))
      (node (ref "IC7") (pin "8") (pinfunction "VCC_8") (pintype "bidirectional"))
      (node (ref "IC8") (pin "4") (pinfunction "VDD_4") (pintype "bidirectional"))
      (node (ref "R1") (pin "2") (pinfunction "2_2") (pintype "passive"))
      (node (ref "R11") (pin "1") (pinfunction "1_1") (pintype "passive"))
      (node (ref "R12") (pin "2") (pinfunction "2_2") (pintype "passive"))
      (node (ref "R13") (pin "2") (pinfunction "2_2") (pintype "passive"))
      (node (ref "R2") (pin "2") (pinfunction "2_2") (pintype "passive"))
      (node (ref "RJ11_1") (pin "P$1") (pinfunction "1_P$1") (pintype "bidirectional"))
      (node (ref "U$1") (pin "3.3V") (pinfunction "3.3V_3.3V") (pintype "bidirectional"))
      (node (ref "U$1") (pin "3V3") (pinfunction "3V3_3V3") (pintype "bidirectional"))
    )
    (net (code "41") (name "VCC_5V") (class "Default")
      (node (ref "C7") (pin "1") (pinfunction "1_1") (pintype "passive"))
      (node (ref "IC3") (pin "3") (pinfunction "INPUT_3") (pintype "bidirectional"))
      (node (ref "U$1") (pin "5V") (pinfunction "5V_5V") (pintype "bidirectional"))
      (node (ref "U$2") (pin "OUT+") (pinfunction "OUT+_OUT+") (pintype "bidirectional"))
    )
    (net (code "42") (name "VCC_12V") (class "Default")
      (node (ref "IC6") (pin "3") (pinfunction "IP-_3") (pintype "passive"))
      (node (ref "IC6") (pin "4") (pinfunction "IP-1_4") (pintype "passive"))
      (node (ref "J1") (pin "2") (pinfunction "2_2") (pintype "passive"))
      (node (ref "R9") (pin "1") (pinfunction "1_1") (pintype "passive"))
      (node (ref "U$2") (pin "IN+") (pinfunction "IN+_IN+") (pintype "bidirectional"))
    )
    (net (code "43") (name "VCC_BBANK") (class "Default")
      (node (ref "BBANK") (pin "1") (pinfunction "1_1") (pintype "bidirectional"))
      (node (ref "R5") (pin "1") (pinfunction "1_1") (pintype "passive"))
    )
    (net (code "44") (name "VCC_PV") (class "Default")
      (node (ref "R7") (pin "1") (pinfunction "1_1") (pintype "passive"))
      (node (ref "VPV") (pin "1") (pinfunction "1_1") (pintype "bidirectional"))
    )
    (net (code "45") (name "unconnected-(IC1-NC-Pad4)") (class "Default")
      (node (ref "IC1") (pin "4") (pinfunction "NC_4") (pintype "no_connect"))
    )
    (net (code "46") (name "unconnected-(IC5-ALERT{slash}RDY-Pad2)") (class "Default")
      (node (ref "IC5") (pin "2") (pinfunction "ALERT/RDY_2") (pintype "bidirectional"))
    )
    (net (code "47") (name "unconnected-(IC8-NC_1-Pad1)") (class "Default")
      (node (ref "IC8") (pin "1") (pinfunction "NC_1_1") (pintype "bidirectional"))
    )
    (net (code "48") (name "unconnected-(IC8-NC_2-Pad5)") (class "Default")
      (node (ref "IC8") (pin "5") (pinfunction "NC_2_5") (pintype "bidirectional"))
    )
    (net (code "49") (name "unconnected-(J2-Pad1)") (class "Default")
      (node (ref "J2") (pin "1") (pinfunction "1_1") (pintype "bidirectional"))
    )
    (net (code "50") (name "unconnected-(J2-Pad2)") (class "Default")
      (node (ref "J2") (pin "2") (pinfunction "2_2") (pintype "bidirectional"))
    )
    (net (code "51") (name "unconnected-(J2-Pad3)") (class "Default")
      (node (ref "J2") (pin "3") (pinfunction "3_3") (pintype "bidirectional"))
    )
    (net (code "52") (name "unconnected-(J2-Pad4)") (class "Default")
      (node (ref "J2") (pin "4") (pinfunction "4_4") (pintype "bidirectional"))
    )
    (net (code "53") (name "unconnected-(J3-Pad1)") (class "Default")
      (node (ref "J3") (pin "1") (pinfunction "1_1") (pintype "bidirectional"))
    )
    (net (code "54") (name "unconnected-(J3-Pad2)") (class "Default")
      (node (ref "J3") (pin "2") (pinfunction "2_2") (pintype "bidirectional"))
    )
    (net (code "55") (name "unconnected-(J3-Pad3)") (class "Default")
      (node (ref "J3") (pin "3") (pinfunction "3_3") (pintype "bidirectional"))
    )
    (net (code "56") (name "unconnected-(J3-Pad4)") (class "Default")
      (node (ref "J3") (pin "4") (pinfunction "4_4") (pintype "bidirectional"))
    )
    (net (code "57") (name "unconnected-(J4-Pad1)") (class "Default")
      (node (ref "J4") (pin "1") (pinfunction "1_1") (pintype "bidirectional"))
    )
    (net (code "58") (name "unconnected-(J4-Pad2)") (class "Default")
      (node (ref "J4") (pin "2") (pinfunction "2_2") (pintype "bidirectional"))
    )
    (net (code "59") (name "unconnected-(J4-Pad3)") (class "Default")
      (node (ref "J4") (pin "3") (pinfunction "3_3") (pintype "bidirectional"))
    )
    (net (code "60") (name "unconnected-(J4-Pad4)") (class "Default")
      (node (ref "J4") (pin "4") (pinfunction "4_4") (pintype "bidirectional"))
    )
    (net (code "61") (name "unconnected-(J5-Pad1)") (class "Default")
      (node (ref "J5") (pin "1") (pinfunction "1_1") (pintype "bidirectional"))
    )
    (net (code "62") (name "unconnected-(J5-Pad2)") (class "Default")
      (node (ref "J5") (pin "2") (pinfunction "2_2") (pintype "bidirectional"))
    )
    (net (code "63") (name "unconnected-(J5-Pad3)") (class "Default")
      (node (ref "J5") (pin "3") (pinfunction "3_3") (pintype "bidirectional"))
    )
    (net (code "64") (name "unconnected-(J5-Pad4)") (class "Default")
      (node (ref "J5") (pin "4") (pinfunction "4_4") (pintype "bidirectional"))
    )
    (net (code "65") (name "~{RXEN}") (class "Default")
      (node (ref "IC7") (pin "2") (pinfunction "~{RE}_2") (pintype "bidirectional"))
      (node (ref "R12") (pin "1") (pinfunction "1_1") (pintype "passive"))
      (node (ref "U$1") (pin "23") (pinfunction "23_23") (pintype "bidirectional"))
    )
  )
)
